# BMS-Shield.net
KiCad netlist of a schematic drawn in EAGLE
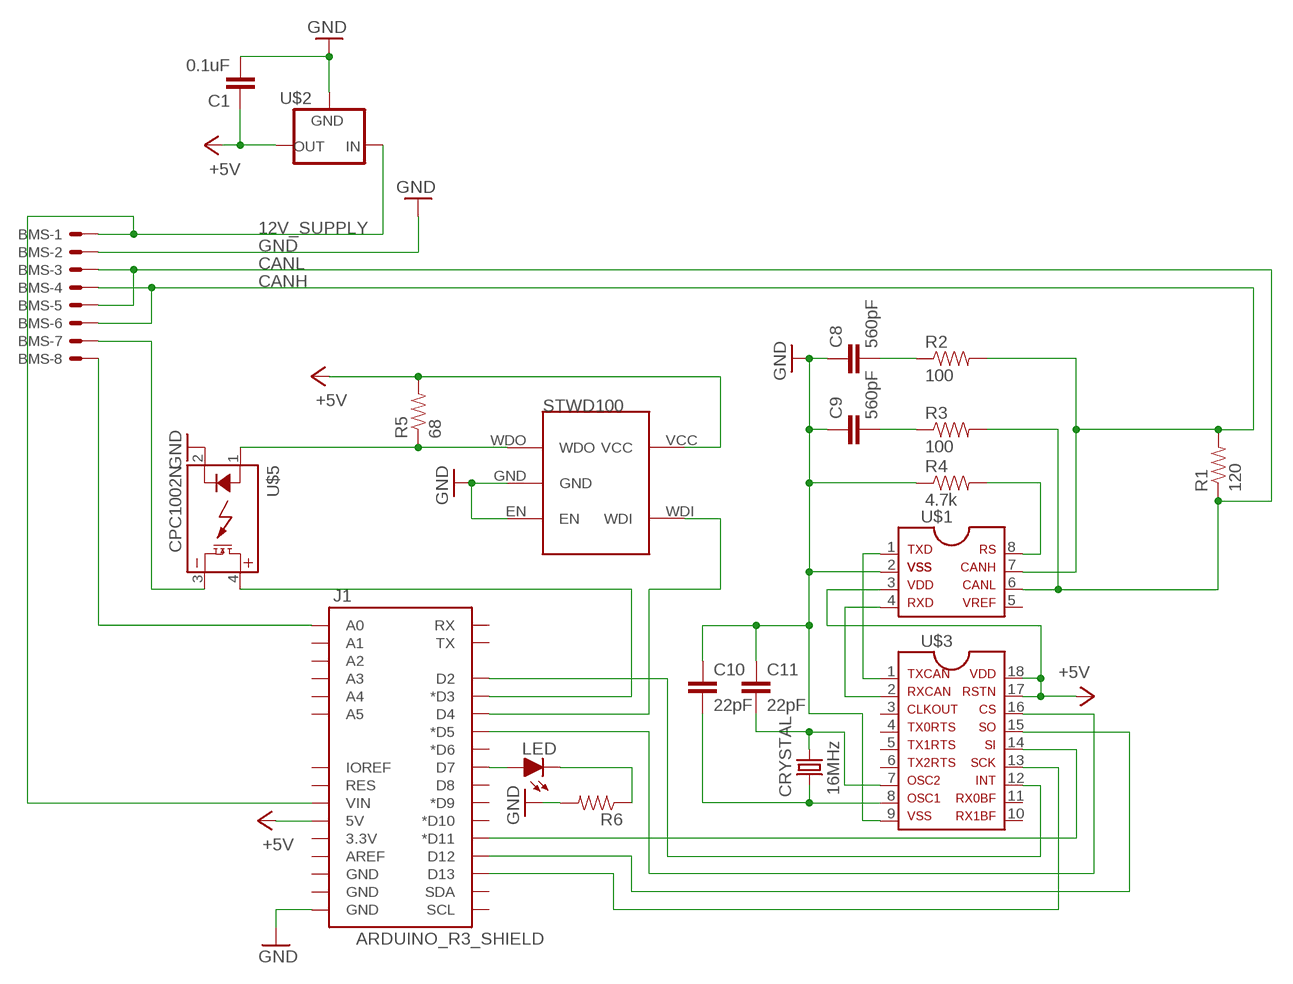
[diagram p0: schematic, sheet 1]

(export (version "E")
  (design (tool "Eeschema 10.0.6"))
  (components
    (comp (ref "BMS")
      (value "MINIFIT_5566-8")
      (footprint "eagle-import:MINIFIT_5566-8")
      (libsource (lib "eagle-import") (part "MINIFIT_5566-8"))
    )
    (comp (ref "C1")
      (value "0.1uF")
      (footprint "eagle-import:0805@1")
      (libsource (lib "eagle-import") (part "CAP0805"))
    )
    (comp (ref "C8")
      (value "560pF")
      (footprint "eagle-import:0805@1")
      (libsource (lib "eagle-import") (part "CAP0805"))
    )
    (comp (ref "C9")
      (value "560pF")
      (footprint "eagle-import:0805@1")
      (libsource (lib "eagle-import") (part "CAP0805"))
    )
    (comp (ref "C10")
      (value "22pF")
      (footprint "eagle-import:0805@1")
      (libsource (lib "eagle-import") (part "CAP0805"))
    )
    (comp (ref "C11")
      (value "22pF")
      (footprint "eagle-import:0805@1")
      (libsource (lib "eagle-import") (part "CAP0805"))
    )
    (comp (ref "CRYSTAL")
      (value "16MHz")
      (footprint "eagle-import:HC49UP")
      (libsource (lib "eagle-import") (part "CRYSTALSMD"))
    )
    (comp (ref "J1")
      (value "ARDUINO_R3_SHIELD")
      (footprint "eagle-import:UNO_R3_SHIELD")
      (libsource (lib "eagle-import") (part "ARDUINO_R3_SHIELD"))
    )
    (comp (ref "LED")
      (value "LED-0805")
      (footprint "eagle-import:LED-805")
      (libsource (lib "eagle-import") (part "LED-0805"))
    )
    (comp (ref "R1")
      (value "120")
      (footprint "eagle-import:0805")
      (libsource (lib "eagle-import") (part "RESISTOR0805-RES"))
    )
    (comp (ref "R2")
      (value "100")
      (footprint "eagle-import:0805")
      (libsource (lib "eagle-import") (part "RESISTOR0805-RES"))
    )
    (comp (ref "R3")
      (value "100")
      (footprint "eagle-import:0805")
      (libsource (lib "eagle-import") (part "RESISTOR0805-RES"))
    )
    (comp (ref "R4")
      (value "4.7k")
      (footprint "eagle-import:0805")
      (libsource (lib "eagle-import") (part "RESISTOR0805-RES"))
    )
    (comp (ref "R5")
      (value "68")
      (footprint "eagle-import:0805")
      (libsource (lib "eagle-import") (part "RESISTOR0805-RES"))
    )
    (comp (ref "R6")
      (value "RESISTOR0805-RES")
      (footprint "eagle-import:0805")
      (libsource (lib "eagle-import") (part "RESISTOR0805-RES"))
    )
    (comp (ref "U$1")
      (value "MCP2551")
      (footprint "eagle-import:SOIC-08")
      (libsource (lib "eagle-import") (part "MCP2551"))
    )
    (comp (ref "U$2")
      (value "5VREG_LM340-NLM340MPX-5.0/NOPB")
      (footprint "eagle-import:SOT223")
      (libsource (lib "eagle-import") (part "5VREG_LM340-NLM340MPX-5.0/NOPB"))
    )
    (comp (ref "U$3")
      (value "MCP2515SMD")
      (footprint "eagle-import:SOIC-18W")
      (libsource (lib "eagle-import") (part "MCP2515SMD"))
    )
    (comp (ref "U$4")
      (value "STWD100")
      (footprint "eagle-import:SOT23-5")
      (libsource (lib "eagle-import") (part "STWD100"))
    )
    (comp (ref "U$5")
      (value "CPC1002N")
      (footprint "eagle-import:SOP04")
      (libsource (lib "eagle-import") (part "CPC1002N"))
    )
  )
  (nets
    (net (code "1") (name "+5V") (class "Default")
      (node (ref "C1") (pin "1") (pinfunction "1_1") (pintype "passive"))
      (node (ref "J1") (pin "5V") (pinfunction "5V_5V") (pintype "bidirectional"))
      (node (ref "R5") (pin "2") (pinfunction "2_2") (pintype "passive"))
      (node (ref "U$1") (pin "3") (pinfunction "3_3") (pintype "passive"))
      (node (ref "U$2") (pin "3") (pinfunction "OUT_3") (pintype "output"))
      (node (ref "U$3") (pin "17") (pinfunction "17_17") (pintype "passive"))
      (node (ref "U$3") (pin "18") (pinfunction "18_18") (pintype "passive"))
      (node (ref "U$4") (pin "VCC") (pinfunction "VCC_VCC") (pintype "bidirectional"))
    )
    (net (code "2") (name "/12V_SUPPLY") (class "Default")
      (node (ref "BMS") (pin "1") (pinfunction "S_1") (pintype "passive"))
      (node (ref "J1") (pin "VIN") (pinfunction "VIN_VIN") (pintype "bidirectional"))
      (node (ref "U$2") (pin "1") (pinfunction "IN_1") (pintype "input"))
    )
    (net (code "3") (name "/CANH") (class "Default")
      (node (ref "BMS") (pin "4") (pinfunction "S_4") (pintype "passive"))
      (node (ref "BMS") (pin "6") (pinfunction "S_6") (pintype "passive"))
      (node (ref "R1") (pin "2") (pinfunction "2_2") (pintype "passive"))
      (node (ref "R2") (pin "2") (pinfunction "2_2") (pintype "passive"))
      (node (ref "U$1") (pin "7") (pinfunction "7_7") (pintype "passive"))
    )
    (net (code "4") (name "/CANL") (class "Default")
      (node (ref "BMS") (pin "3") (pinfunction "S_3") (pintype "passive"))
      (node (ref "BMS") (pin "5") (pinfunction "S_5") (pintype "passive"))
      (node (ref "R1") (pin "1") (pinfunction "1_1") (pintype "passive"))
      (node (ref "R3") (pin "2") (pinfunction "2_2") (pintype "passive"))
      (node (ref "U$1") (pin "6") (pinfunction "6_6") (pintype "passive"))
    )
    (net (code "5") (name "GND") (class "Default")
      (node (ref "BMS") (pin "2") (pinfunction "S_2") (pintype "passive"))
      (node (ref "C1") (pin "2") (pinfunction "2_2") (pintype "passive"))
      (node (ref "C10") (pin "1") (pinfunction "1_1") (pintype "passive"))
      (node (ref "C11") (pin "1") (pinfunction "1_1") (pintype "passive"))
      (node (ref "C8") (pin "1") (pinfunction "1_1") (pintype "passive"))
      (node (ref "C9") (pin "1") (pinfunction "1_1") (pintype "passive"))
      (node (ref "J1") (pin "GND@0") (pinfunction "GND_GND@0") (pintype "bidirectional"))
      (node (ref "R4") (pin "1") (pinfunction "1_1") (pintype "passive"))
      (node (ref "R6") (pin "2") (pinfunction "2_2") (pintype "passive"))
      (node (ref "U$1") (pin "2") (pinfunction "2_2") (pintype "passive"))
      (node (ref "U$2") (pin "2") (pinfunction "GND_2") (pintype "input"))
      (node (ref "U$2") (pin "4") (pinfunction "GND_4") (pintype "input"))
      (node (ref "U$3") (pin "9") (pinfunction "9_9") (pintype "passive"))
      (node (ref "U$4") (pin "EN") (pinfunction "EN_EN") (pintype "bidirectional"))
      (node (ref "U$4") (pin "GND") (pinfunction "GND_GND") (pintype "bidirectional"))
      (node (ref "U$5") (pin "2") (pinfunction "CONTROL-_2") (pintype "passive"))
    )
    (net (code "6") (name "Net-(BMSG-S)") (class "Default")
      (node (ref "BMS") (pin "7") (pinfunction "S_7") (pintype "passive"))
      (node (ref "U$5") (pin "3") (pinfunction "DC-_3") (pintype "passive"))
    )
    (net (code "7") (name "Net-(BMSH-S)") (class "Default")
      (node (ref "BMS") (pin "8") (pinfunction "S_8") (pintype "passive"))
      (node (ref "J1") (pin "A0") (pinfunction "A0_A0") (pintype "bidirectional"))
    )
    (net (code "8") (name "Net-(C8-Pad2)") (class "Default")
      (node (ref "C8") (pin "2") (pinfunction "2_2") (pintype "passive"))
      (node (ref "R2") (pin "1") (pinfunction "1_1") (pintype "passive"))
    )
    (net (code "9") (name "Net-(C9-Pad2)") (class "Default")
      (node (ref "C9") (pin "2") (pinfunction "2_2") (pintype "passive"))
      (node (ref "R3") (pin "1") (pinfunction "1_1") (pintype "passive"))
    )
    (net (code "10") (name "Net-(C10-Pad2)") (class "Default")
      (node (ref "C10") (pin "2") (pinfunction "2_2") (pintype "passive"))
      (node (ref "CRYSTAL") (pin "2") (pinfunction "2_2") (pintype "passive"))
      (node (ref "U$3") (pin "8") (pinfunction "8_8") (pintype "passive"))
    )
    (net (code "11") (name "Net-(C11-Pad2)") (class "Default")
      (node (ref "C11") (pin "2") (pinfunction "2_2") (pintype "passive"))
      (node (ref "CRYSTAL") (pin "1") (pinfunction "1_1") (pintype "passive"))
      (node (ref "U$3") (pin "7") (pinfunction "7_7") (pintype "passive"))
    )
    (net (code "12") (name "Net-(J1-*D3)") (class "Default")
      (node (ref "J1") (pin "D3") (pinfunction "*D3_D3") (pintype "bidirectional"))
      (node (ref "U$5") (pin "4") (pinfunction "DC+_4") (pintype "passive"))
    )
    (net (code "13") (name "Net-(J1-*D5)") (class "Default")
      (node (ref "J1") (pin "D5") (pinfunction "*D5_D5") (pintype "bidirectional"))
      (node (ref "U$3") (pin "16") (pinfunction "16_16") (pintype "passive"))
    )
    (net (code "14") (name "Net-(J1-*D11)") (class "Default")
      (node (ref "J1") (pin "D11") (pinfunction "*D11_D11") (pintype "bidirectional"))
      (node (ref "U$3") (pin "14") (pinfunction "14_14") (pintype "passive"))
    )
    (net (code "15") (name "Net-(J1-PadD2)") (class "Default")
      (node (ref "J1") (pin "D2") (pinfunction "D2_D2") (pintype "bidirectional"))
      (node (ref "U$3") (pin "12") (pinfunction "12_12") (pintype "passive"))
    )
    (net (code "16") (name "Net-(J1-PadD4)") (class "Default")
      (node (ref "J1") (pin "D4") (pinfunction "D4_D4") (pintype "bidirectional"))
      (node (ref "U$4") (pin "WDI") (pinfunction "WDI_WDI") (pintype "bidirectional"))
    )
    (net (code "17") (name "Net-(J1-PadD7)") (class "Default")
      (node (ref "J1") (pin "D7") (pinfunction "D7_D7") (pintype "bidirectional"))
      (node (ref "LED") (pin "A") (pinfunction "A_A") (pintype "passive"))
    )
    (net (code "18") (name "Net-(J1-PadD12)") (class "Default")
      (node (ref "J1") (pin "D12") (pinfunction "D12_D12") (pintype "bidirectional"))
      (node (ref "U$3") (pin "15") (pinfunction "15_15") (pintype "passive"))
    )
    (net (code "19") (name "Net-(J1-PadD13)") (class "Default")
      (node (ref "J1") (pin "D13") (pinfunction "D13_D13") (pintype "bidirectional"))
      (node (ref "U$3") (pin "13") (pinfunction "13_13") (pintype "passive"))
    )
    (net (code "20") (name "Net-(LED-PadC)") (class "Default")
      (node (ref "LED") (pin "C") (pinfunction "C_C") (pintype "passive"))
      (node (ref "R6") (pin "1") (pinfunction "1_1") (pintype "passive"))
    )
    (net (code "21") (name "Net-(R4-Pad2)") (class "Default")
      (node (ref "R4") (pin "2") (pinfunction "2_2") (pintype "passive"))
      (node (ref "U$1") (pin "8") (pinfunction "8_8") (pintype "passive"))
    )
    (net (code "22") (name "Net-(U$1-Pad1)") (class "Default")
      (node (ref "U$1") (pin "1") (pinfunction "1_1") (pintype "passive"))
      (node (ref "U$3") (pin "1") (pinfunction "1_1") (pintype "passive"))
    )
    (net (code "23") (name "Net-(U$1-Pad4)") (class "Default")
      (node (ref "U$1") (pin "4") (pinfunction "4_4") (pintype "passive"))
      (node (ref "U$3") (pin "2") (pinfunction "2_2") (pintype "passive"))
    )
    (net (code "24") (name "Net-(U$5-CONTROL+)") (class "Default")
      (node (ref "R5") (pin "1") (pinfunction "1_1") (pintype "passive"))
      (node (ref "U$4") (pin "WDO") (pinfunction "WDO_WDO") (pintype "bidirectional"))
      (node (ref "U$5") (pin "1") (pinfunction "CONTROL+_1") (pintype "passive"))
    )
    (net (code "25") (name "unconnected-(J1-*D6-PadD6)") (class "Default")
      (node (ref "J1") (pin "D6") (pinfunction "*D6_D6") (pintype "bidirectional"))
    )
    (net (code "26") (name "unconnected-(J1-*D9-PadD9)") (class "Default")
      (node (ref "J1") (pin "D9") (pinfunction "*D9_D9") (pintype "bidirectional"))
    )
    (net (code "27") (name "unconnected-(J1-*D10-PadD10)") (class "Default")
      (node (ref "J1") (pin "D10") (pinfunction "*D10_D10") (pintype "bidirectional"))
    )
    (net (code "28") (name "unconnected-(J1-GND-PadGND@1)") (class "Default")
      (node (ref "J1") (pin "GND@1") (pinfunction "GND_GND@1") (pintype "bidirectional"))
    )
    (net (code "29") (name "unconnected-(J1-GND-PadGND@2)") (class "Default")
      (node (ref "J1") (pin "GND@2") (pinfunction "GND_GND@2") (pintype "bidirectional"))
    )
    (net (code "30") (name "unconnected-(J1-Pad3.3V)") (class "Default")
      (node (ref "J1") (pin "3.3V") (pinfunction "3.3V_3.3V") (pintype "bidirectional"))
    )
    (net (code "31") (name "unconnected-(J1-PadA1)") (class "Default")
      (node (ref "J1") (pin "A1") (pinfunction "A1_A1") (pintype "bidirectional"))
    )
    (net (code "32") (name "unconnected-(J1-PadA2)") (class "Default")
      (node (ref "J1") (pin "A2") (pinfunction "A2_A2") (pintype "bidirectional"))
    )
    (net (code "33") (name "unconnected-(J1-PadA3)") (class "Default")
      (node (ref "J1") (pin "A3") (pinfunction "A3_A3") (pintype "bidirectional"))
    )
    (net (code "34") (name "unconnected-(J1-PadA4)") (class "Default")
      (node (ref "J1") (pin "A4") (pinfunction "A4_A4") (pintype "bidirectional"))
    )
    (net (code "35") (name "unconnected-(J1-PadA5)") (class "Default")
      (node (ref "J1") (pin "A5") (pinfunction "A5_A5") (pintype "bidirectional"))
    )
    (net (code "36") (name "unconnected-(J1-PadAREF)") (class "Default")
      (node (ref "J1") (pin "AREF") (pinfunction "AREF_AREF") (pintype "bidirectional"))
    )
    (net (code "37") (name "unconnected-(J1-PadD8)") (class "Default")
      (node (ref "J1") (pin "D8") (pinfunction "D8_D8") (pintype "bidirectional"))
    )
    (net (code "38") (name "unconnected-(J1-PadIOREF)") (class "Default")
      (node (ref "J1") (pin "IOREF") (pinfunction "IOREF_IOREF") (pintype "bidirectional"))
    )
    (net (code "39") (name "unconnected-(J1-PadRES)") (class "Default")
      (node (ref "J1") (pin "RES") (pinfunction "RES_RES") (pintype "bidirectional"))
    )
    (net (code "40") (name "unconnected-(J1-PadRX)") (class "Default")
      (node (ref "J1") (pin "RX") (pinfunction "RX_RX") (pintype "bidirectional"))
    )
    (net (code "41") (name "unconnected-(J1-PadSCL)") (class "Default")
      (node (ref "J1") (pin "SCL") (pinfunction "SCL_SCL") (pintype "bidirectional"))
    )
    (net (code "42") (name "unconnected-(J1-PadSDA)") (class "Default")
      (node (ref "J1") (pin "SDA") (pinfunction "SDA_SDA") (pintype "bidirectional"))
    )
    (net (code "43") (name "unconnected-(J1-PadTX)") (class "Default")
      (node (ref "J1") (pin "TX") (pinfunction "TX_TX") (pintype "bidirectional"))
    )
    (net (code "44") (name "unconnected-(U$1-Pad5)") (class "Default")
      (node (ref "U$1") (pin "5") (pinfunction "5_5") (pintype "passive"))
    )
    (net (code "45") (name "unconnected-(U$3-Pad3)") (class "Default")
      (node (ref "U$3") (pin "3") (pinfunction "3_3") (pintype "passive"))
    )
    (net (code "46") (name "unconnected-(U$3-Pad4)") (class "Default")
      (node (ref "U$3") (pin "4") (pinfunction "4_4") (pintype "passive"))
    )
    (net (code "47") (name "unconnected-(U$3-Pad5)") (class "Default")
      (node (ref "U$3") (pin "5") (pinfunction "5_5") (pintype "passive"))
    )
    (net (code "48") (name "unconnected-(U$3-Pad6)") (class "Default")
      (node (ref "U$3") (pin "6") (pinfunction "6_6") (pintype "passive"))
    )
    (net (code "49") (name "unconnected-(U$3-Pad10)") (class "Default")
      (node (ref "U$3") (pin "10") (pinfunction "10_10") (pintype "passive"))
    )
    (net (code "50") (name "unconnected-(U$3-Pad11)") (class "Default")
      (node (ref "U$3") (pin "11") (pinfunction "11_11") (pintype "passive"))
    )
  )
)
